# Codeshelf-0005_v01.net
KiCad netlist of a schematic drawn in EAGLE
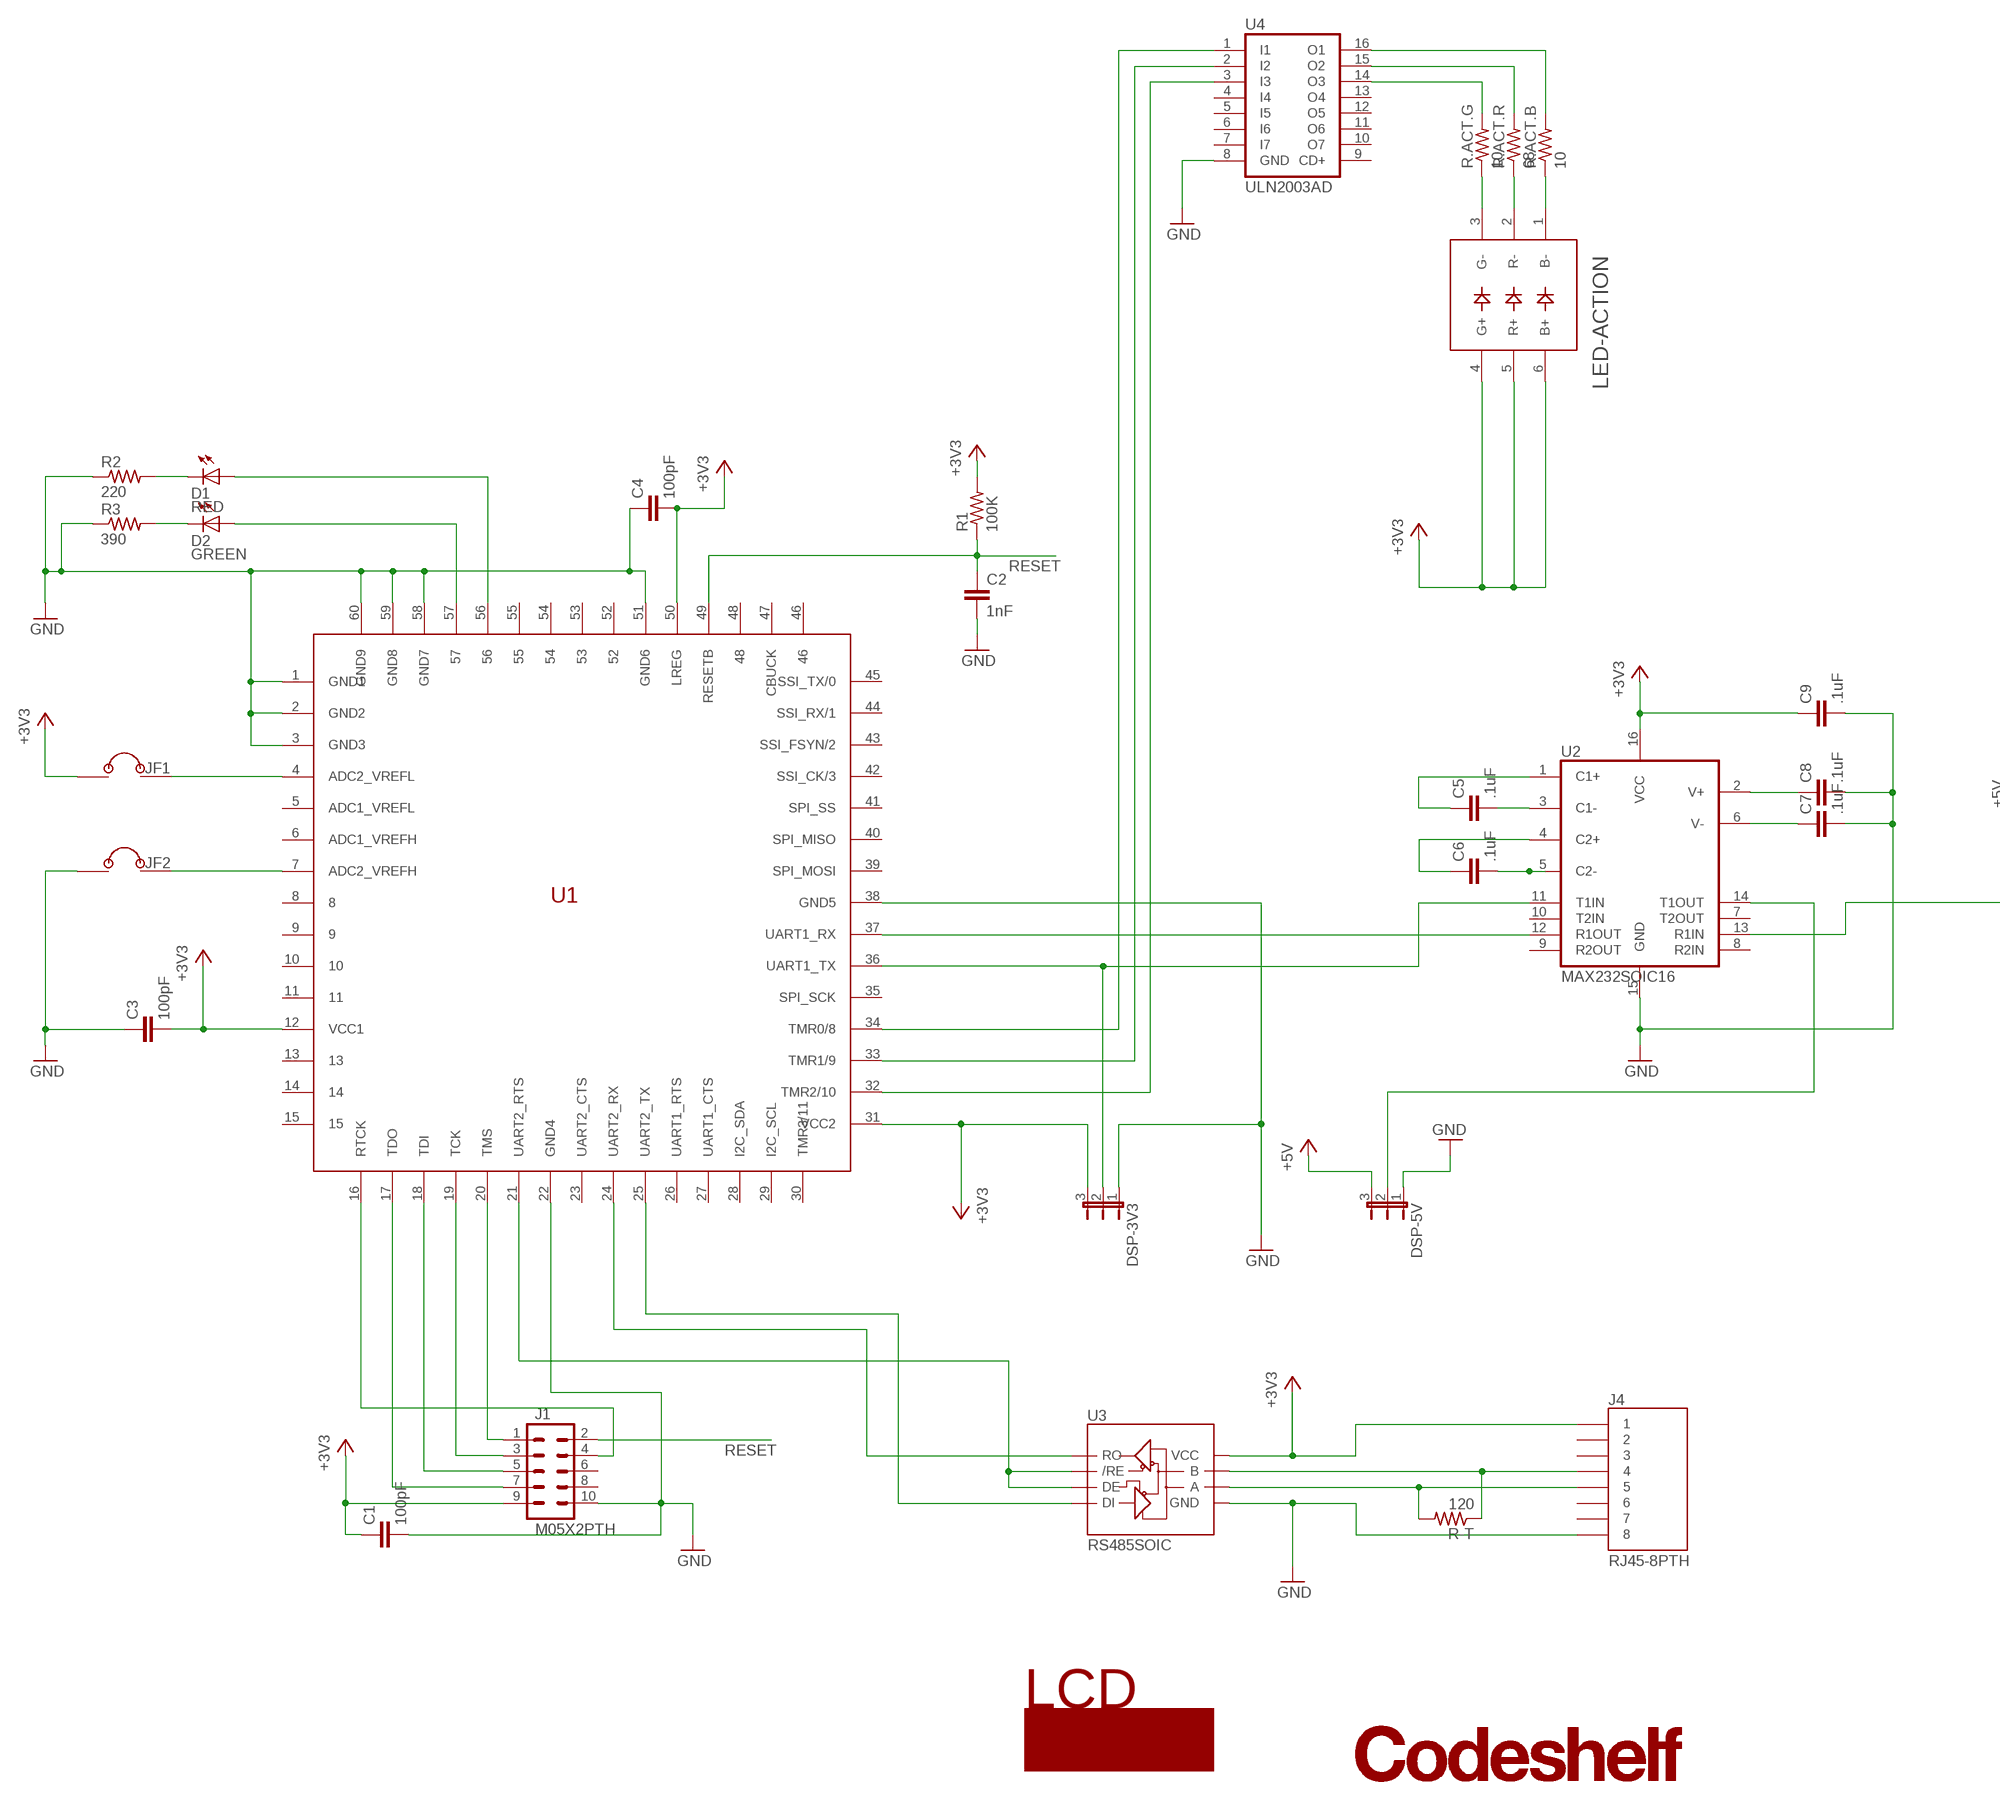
[diagram p0: schematic, sheet 1, part 1 of 2]
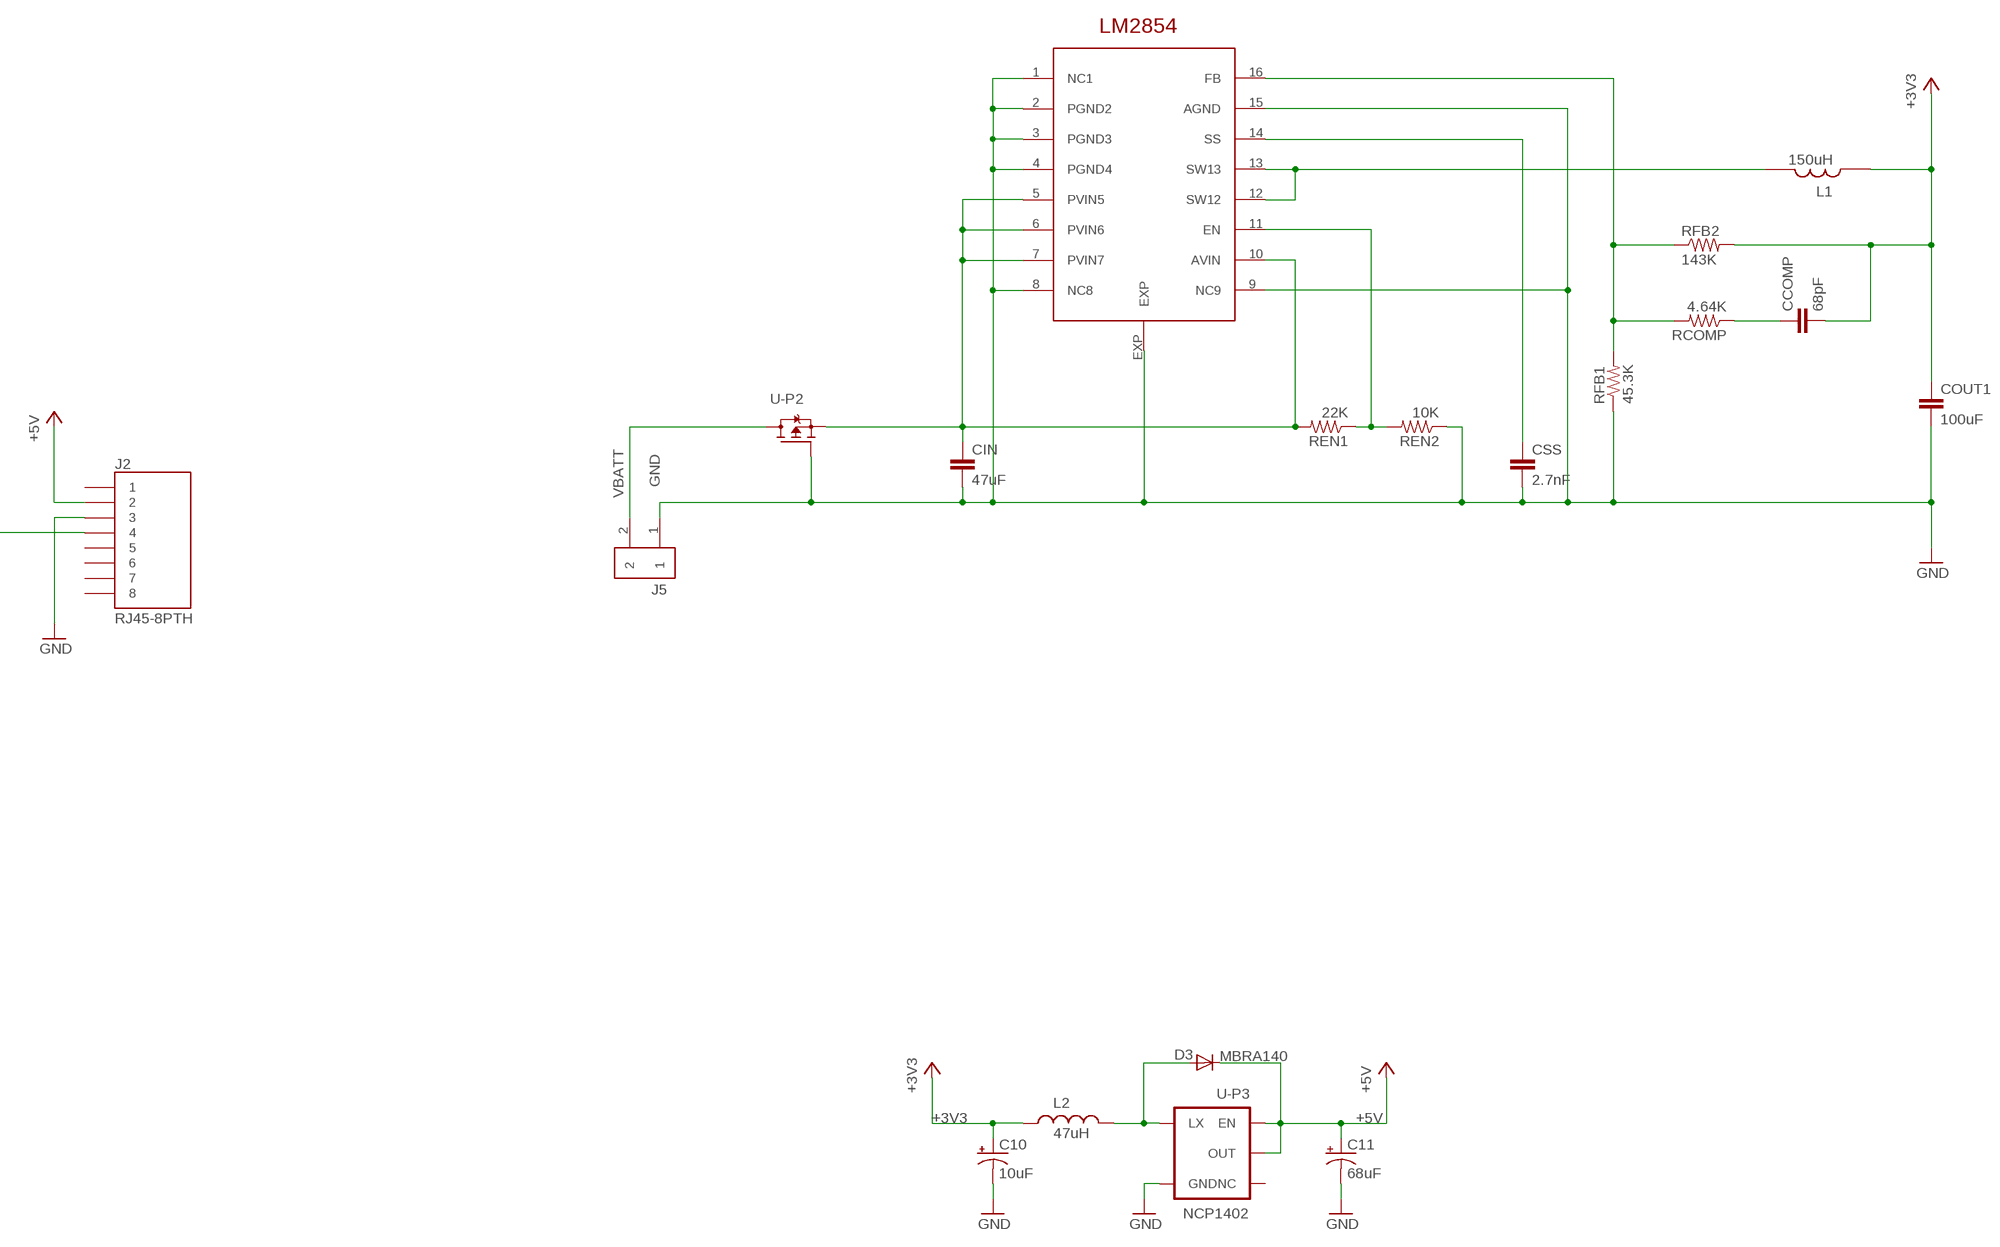
[diagram p1: schematic, sheet 1, part 2 of 2]

(export (version "E")
  (design (tool "Eeschema 10.0.6"))
  (components
    (comp (ref "C1")
      (value "100pF")
      (footprint "eagle-import:C0603")
      (libsource (lib "eagle-import") (part "RF-C0603"))
    )
    (comp (ref "C2")
      (value "1nF")
      (footprint "eagle-import:C0603")
      (libsource (lib "eagle-import") (part "RF-C0603"))
    )
    (comp (ref "C3")
      (value "100pF")
      (footprint "eagle-import:C0603")
      (libsource (lib "eagle-import") (part "RF-C0603"))
    )
    (comp (ref "C4")
      (value "100pF")
      (footprint "eagle-import:C0603")
      (libsource (lib "eagle-import") (part "RF-C0603"))
    )
    (comp (ref "C5")
      (value ".1uF")
      (footprint "eagle-import:C0402")
      (libsource (lib "eagle-import") (part "RF-C0402"))
    )
    (comp (ref "C6")
      (value ".1uF")
      (footprint "eagle-import:C0402")
      (libsource (lib "eagle-import") (part "RF-C0402"))
    )
    (comp (ref "C7")
      (value ".1uF")
      (footprint "eagle-import:C0402")
      (libsource (lib "eagle-import") (part "RF-C0402"))
    )
    (comp (ref "C8")
      (value ".1uF")
      (footprint "eagle-import:C0402")
      (libsource (lib "eagle-import") (part "RF-C0402"))
    )
    (comp (ref "C9")
      (value ".1uF")
      (footprint "eagle-import:C0402")
      (libsource (lib "eagle-import") (part "RF-C0402"))
    )
    (comp (ref "C10")
      (value "10uF")
      (footprint "eagle-import:EIA3216")
      (libsource (lib "eagle-import") (part "CAP_POL1206"))
    )
    (comp (ref "C11")
      (value "68uF")
      (footprint "eagle-import:EIA3528")
      (libsource (lib "eagle-import") (part "CAP_POL3528"))
    )
    (comp (ref "CCOMP")
      (value "68pF")
      (footprint "eagle-import:C0805")
      (libsource (lib "eagle-import") (part "RF-C0805"))
    )
    (comp (ref "CIN")
      (value "47uF")
      (footprint "eagle-import:C1210K")
      (libsource (lib "eagle-import") (part "RF-C1210"))
    )
    (comp (ref "COUT1")
      (value "100uF")
      (footprint "eagle-import:C1210K")
      (libsource (lib "eagle-import") (part "RF-C1210"))
    )
    (comp (ref "CSS")
      (value "2.7nF")
      (footprint "eagle-import:C0805")
      (libsource (lib "eagle-import") (part "RF-C0805"))
    )
    (comp (ref "D1")
      (value "RED")
      (footprint "eagle-import:CHIP-LED0805")
      (libsource (lib "eagle-import") (part "LEDCHIP-LED0805"))
    )
    (comp (ref "D2")
      (value "GREEN")
      (footprint "eagle-import:CHIP-LED0805")
      (libsource (lib "eagle-import") (part "LEDCHIP-LED0805"))
    )
    (comp (ref "D3")
      (value "MBRA140")
      (footprint "eagle-import:SMA-DIODE")
      (libsource (lib "eagle-import") (part "DIODESMA"))
    )
    (comp (ref "DSP-3V3")
      (value "JUMPER-3PTH")
      (footprint "eagle-import:1X03")
      (libsource (lib "eagle-import") (part "JUMPER-3PTH"))
    )
    (comp (ref "DSP-5V")
      (value "JUMPER-3PTH")
      (footprint "eagle-import:1X03")
      (libsource (lib "eagle-import") (part "JUMPER-3PTH"))
    )
    (comp (ref "J1")
      (value "M05X2PTH")
      (footprint "eagle-import:AVR_ICSP")
      (libsource (lib "eagle-import") (part "M05X2PTH"))
    )
    (comp (ref "J2")
      (value "RJ45-8PTH")
      (footprint "eagle-import:RJ45-8")
      (libsource (lib "eagle-import") (part "RJ45-8PTH"))
    )
    (comp (ref "J4")
      (value "RJ45-8PTH")
      (footprint "eagle-import:RJ45-8")
      (libsource (lib "eagle-import") (part "RJ45-8PTH"))
    )
    (comp (ref "J5")
      (value "HEADER-2X-2.54MM")
      (footprint "eagle-import:HEADER-2X-RA-2.54MM")
      (libsource (lib "eagle-import") (part "HEADER-2X-2.54MM"))
    )
    (comp (ref "JF1")
      (value "JUMPER-2X-SMT-VIA")
      (footprint "eagle-import:JUMPER-VIA-2X")
      (libsource (lib "eagle-import") (part "JUMPER-2X-SMT-VIA"))
    )
    (comp (ref "JF2")
      (value "JUMPER-2X-SMT-VIA")
      (footprint "eagle-import:JUMPER-VIA-2X")
      (libsource (lib "eagle-import") (part "JUMPER-2X-SMT-VIA"))
    )
    (comp (ref "L1")
      (value "150uH")
      (footprint "eagle-import:SLF10165")
      (libsource (lib "eagle-import") (part "INDUCTOR-SMD-UNUSUAL-SLF10165"))
    )
    (comp (ref "L2")
      (value "47uH")
      (footprint "eagle-import:CR54")
      (libsource (lib "eagle-import") (part "INDUCTORCR54"))
    )
    (comp (ref "LCD")
      (value "LCD-SPARKFUN")
      (footprint "eagle-import:LCD-20X4-SPARKFUN")
      (libsource (lib "eagle-import") (part "LCD-SPARKFUN20X4"))
    )
    (comp (ref "LED-ACTION")
      (value "LED5060A")
      (footprint "eagle-import:PLCC-6")
      (libsource (lib "eagle-import") (part "LED5060A"))
    )
    (comp (ref "LOGO")
      (value "CODESHELF-LOGO")
      (footprint "eagle-import:CODESHELF-LOGO")
      (libsource (lib "eagle-import") (part "CODESHELF-LOGO"))
    )
    (comp (ref "R-T")
      (value "120")
      (footprint "eagle-import:RF-R0402")
      (libsource (lib "eagle-import") (part "RF-R0402"))
    )
    (comp (ref "R.ACT.B")
      (value "10")
      (footprint "eagle-import:RF-R0402")
      (libsource (lib "eagle-import") (part "RF-R0402"))
    )
    (comp (ref "R.ACT.G")
      (value "10")
      (footprint "eagle-import:RF-R0402")
      (libsource (lib "eagle-import") (part "RF-R0402"))
    )
    (comp (ref "R.ACT.R")
      (value "68")
      (footprint "eagle-import:RF-R0402")
      (libsource (lib "eagle-import") (part "RF-R0402"))
    )
    (comp (ref "R1")
      (value "100K")
      (footprint "eagle-import:RF-R0402")
      (libsource (lib "eagle-import") (part "RF-R0402"))
    )
    (comp (ref "R2")
      (value "220")
      (footprint "eagle-import:RF-R0402")
      (libsource (lib "eagle-import") (part "RF-R0402"))
    )
    (comp (ref "R3")
      (value "390")
      (footprint "eagle-import:RF-R0402")
      (libsource (lib "eagle-import") (part "RF-R0402"))
    )
    (comp (ref "RCOMP")
      (value "4.64K")
      (footprint "eagle-import:RF-R0402")
      (libsource (lib "eagle-import") (part "RF-R0402"))
    )
    (comp (ref "REN1")
      (value "22K")
      (footprint "eagle-import:RF-R0402")
      (libsource (lib "eagle-import") (part "RF-R0402"))
    )
    (comp (ref "REN2")
      (value "10K")
      (footprint "eagle-import:RF-R0402")
      (libsource (lib "eagle-import") (part "RF-R0402"))
    )
    (comp (ref "RFB1")
      (value "45.3K")
      (footprint "eagle-import:RF-R0402")
      (libsource (lib "eagle-import") (part "RF-R0402"))
    )
    (comp (ref "RFB2")
      (value "143K")
      (footprint "eagle-import:RF-R0402")
      (libsource (lib "eagle-import") (part "RF-R0402"))
    )
    (comp (ref "U-P1")
      (value "LM2854MH")
      (footprint "eagle-import:HTSSOP16PWP")
      (libsource (lib "eagle-import") (part "LM2854MH"))
    )
    (comp (ref "U-P2")
      (value "PCHANNEL-MOSFET-DPAK")
      (footprint "eagle-import:DPAK")
      (libsource (lib "eagle-import") (part "PCHANNEL-MOSFET-DPAK"))
    )
    (comp (ref "U-P3")
      (value "NCP1402")
      (footprint "eagle-import:SOT23-5")
      (libsource (lib "eagle-import") (part "V_REG_NCP1400SOT23-5"))
    )
    (comp (ref "U1")
      (value "ZSFM201-1A")
      (footprint "eagle-import:ZSFM201-1")
      (libsource (lib "eagle-import") (part "ZSFM201-1A"))
    )
    (comp (ref "U2")
      (value "MAX232SOIC16")
      (footprint "eagle-import:SO016")
      (libsource (lib "eagle-import") (part "MAX232SOIC16"))
    )
    (comp (ref "U3")
      (value "RS485SOIC")
      (footprint "eagle-import:SO08")
      (libsource (lib "eagle-import") (part "RS485SOIC"))
    )
    (comp (ref "U4")
      (value "ULN2003AD")
      (footprint "eagle-import:SO16")
      (libsource (lib "eagle-import") (part "ULN2003AD"))
    )
  )
  (nets
    (net (code "1") (name "+3V3") (class "Default")
      (node (ref "C1") (pin "1") (pinfunction "1_1") (pintype "passive"))
      (node (ref "C10") (pin "A") (pinfunction "+_A") (pintype "passive"))
      (node (ref "C3") (pin "2") (pinfunction "2_2") (pintype "passive"))
      (node (ref "C4") (pin "2") (pinfunction "2_2") (pintype "passive"))
      (node (ref "C9") (pin "1") (pinfunction "1_1") (pintype "passive"))
      (node (ref "CCOMP") (pin "2") (pinfunction "2_2") (pintype "passive"))
      (node (ref "COUT1") (pin "1") (pinfunction "1_1") (pintype "passive"))
      (node (ref "DSP-3V3") (pin "3") (pinfunction "3_3") (pintype "passive"))
      (node (ref "J1") (pin "9") (pinfunction "9_9") (pintype "passive"))
      (node (ref "J4") (pin "1") (pinfunction "1_1") (pintype "bidirectional"))
      (node (ref "JF1") (pin "1") (pinfunction "1_1") (pintype "bidirectional"))
      (node (ref "L1") (pin "2") (pinfunction "2_2") (pintype "bidirectional"))
      (node (ref "L2") (pin "P$1") (pinfunction "1_P$1") (pintype "passive"))
      (node (ref "LED-ACTION") (pin "4") (pinfunction "G+_4") (pintype "bidirectional"))
      (node (ref "LED-ACTION") (pin "5") (pinfunction "R+_5") (pintype "bidirectional"))
      (node (ref "LED-ACTION") (pin "6") (pinfunction "B+_6") (pintype "bidirectional"))
      (node (ref "R1") (pin "2") (pinfunction "2_2") (pintype "passive"))
      (node (ref "RFB2") (pin "2") (pinfunction "2_2") (pintype "passive"))
      (node (ref "U1") (pin "12") (pinfunction "VCC1_12") (pintype "power_in"))
      (node (ref "U1") (pin "31") (pinfunction "VCC2_31") (pintype "power_in"))
      (node (ref "U1") (pin "50") (pinfunction "LREG_50") (pintype "bidirectional"))
      (node (ref "U2") (pin "16") (pinfunction "VCC_16") (pintype "bidirectional"))
      (node (ref "U3") (pin "8") (pinfunction "VCC_8") (pintype "bidirectional"))
    )
    (net (code "2") (name "+5V") (class "Default")
      (node (ref "C11") (pin "A") (pinfunction "+_A") (pintype "passive"))
      (node (ref "D3") (pin "C") (pinfunction "C_C") (pintype "passive"))
      (node (ref "DSP-5V") (pin "3") (pinfunction "3_3") (pintype "passive"))
      (node (ref "J2") (pin "2") (pinfunction "2_2") (pintype "bidirectional"))
      (node (ref "U-P3") (pin "1") (pinfunction "EN_1") (pintype "input"))
      (node (ref "U-P3") (pin "2") (pinfunction "OUT_2") (pintype "passive"))
    )
    (net (code "3") (name "/RESET") (class "Default")
      (node (ref "C2") (pin "1") (pinfunction "1_1") (pintype "passive"))
      (node (ref "J1") (pin "2") (pinfunction "2_2") (pintype "passive"))
      (node (ref "R1") (pin "1") (pinfunction "1_1") (pintype "passive"))
      (node (ref "U1") (pin "49") (pinfunction "RESETB_49") (pintype "bidirectional"))
    )
    (net (code "4") (name "/VBATT") (class "Default")
      (node (ref "J5") (pin "2") (pinfunction "2_2") (pintype "bidirectional"))
      (node (ref "U-P2") (pin "4") (pinfunction "D_4") (pintype "passive"))
    )
    (net (code "5") (name "GND") (class "Default")
      (node (ref "C1") (pin "2") (pinfunction "2_2") (pintype "passive"))
      (node (ref "C10") (pin "C") (pinfunction "-_C") (pintype "passive"))
      (node (ref "C11") (pin "C") (pinfunction "-_C") (pintype "passive"))
      (node (ref "C2") (pin "2") (pinfunction "2_2") (pintype "passive"))
      (node (ref "C3") (pin "1") (pinfunction "1_1") (pintype "passive"))
      (node (ref "C4") (pin "1") (pinfunction "1_1") (pintype "passive"))
      (node (ref "C7") (pin "2") (pinfunction "2_2") (pintype "passive"))
      (node (ref "C8") (pin "2") (pinfunction "2_2") (pintype "passive"))
      (node (ref "C9") (pin "2") (pinfunction "2_2") (pintype "passive"))
      (node (ref "CIN") (pin "2") (pinfunction "2_2") (pintype "passive"))
      (node (ref "COUT1") (pin "2") (pinfunction "2_2") (pintype "passive"))
      (node (ref "CSS") (pin "2") (pinfunction "2_2") (pintype "passive"))
      (node (ref "DSP-3V3") (pin "1") (pinfunction "1_1") (pintype "passive"))
      (node (ref "DSP-5V") (pin "1") (pinfunction "1_1") (pintype "passive"))
      (node (ref "J1") (pin "10") (pinfunction "10_10") (pintype "passive"))
      (node (ref "J2") (pin "3") (pinfunction "3_3") (pintype "bidirectional"))
      (node (ref "J4") (pin "8") (pinfunction "8_8") (pintype "bidirectional"))
      (node (ref "J5") (pin "1") (pinfunction "1_1") (pintype "bidirectional"))
      (node (ref "JF2") (pin "1") (pinfunction "1_1") (pintype "bidirectional"))
      (node (ref "R2") (pin "1") (pinfunction "1_1") (pintype "passive"))
      (node (ref "R3") (pin "1") (pinfunction "1_1") (pintype "passive"))
      (node (ref "REN2") (pin "1") (pinfunction "1_1") (pintype "passive"))
      (node (ref "RFB1") (pin "1") (pinfunction "1_1") (pintype "passive"))
      (node (ref "U-P1") (pin "1") (pinfunction "NC1_1") (pintype "bidirectional"))
      (node (ref "U-P1") (pin "15") (pinfunction "AGND_15") (pintype "bidirectional"))
      (node (ref "U-P1") (pin "2") (pinfunction "PGND2_2") (pintype "bidirectional"))
      (node (ref "U-P1") (pin "3") (pinfunction "PGND3_3") (pintype "bidirectional"))
      (node (ref "U-P1") (pin "4") (pinfunction "PGND4_4") (pintype "bidirectional"))
      (node (ref "U-P1") (pin "8") (pinfunction "NC8_8") (pintype "bidirectional"))
      (node (ref "U-P1") (pin "9") (pinfunction "NC9_9") (pintype "bidirectional"))
      (node (ref "U-P1") (pin "EXP") (pinfunction "EXP_EXP") (pintype "bidirectional"))
      (node (ref "U-P2") (pin "1") (pinfunction "G_1") (pintype "passive"))
      (node (ref "U-P3") (pin "4") (pinfunction "GND_4") (pintype "input"))
      (node (ref "U1") (pin "1") (pinfunction "GND1_1") (pintype "power_in"))
      (node (ref "U1") (pin "2") (pinfunction "GND2_2") (pintype "power_in"))
      (node (ref "U1") (pin "22") (pinfunction "GND4_22") (pintype "power_in"))
      (node (ref "U1") (pin "3") (pinfunction "GND3_3") (pintype "power_in"))
      (node (ref "U1") (pin "38") (pinfunction "GND5_38") (pintype "power_in"))
      (node (ref "U1") (pin "51") (pinfunction "GND6_51") (pintype "power_in"))
      (node (ref "U1") (pin "58") (pinfunction "GND7_58") (pintype "power_in"))
      (node (ref "U1") (pin "59") (pinfunction "GND8_59") (pintype "power_in"))
      (node (ref "U1") (pin "60") (pinfunction "GND9_60") (pintype "power_in"))
      (node (ref "U2") (pin "15") (pinfunction "GND_15") (pintype "bidirectional"))
      (node (ref "U3") (pin "5") (pinfunction "GND_5") (pintype "bidirectional"))
      (node (ref "U4") (pin "8") (pinfunction "GND_8") (pintype "power_in"))
    )
    (net (code "6") (name "Net-(CCOMP-Pad1)") (class "Default")
      (node (ref "CCOMP") (pin "1") (pinfunction "1_1") (pintype "passive"))
      (node (ref "RCOMP") (pin "1") (pinfunction "1_1") (pintype "passive"))
    )
    (net (code "7") (name "Net-(D1-PadA)") (class "Default")
      (node (ref "D1") (pin "A") (pinfunction "A_A") (pintype "passive"))
      (node (ref "U1") (pin "56") (pinfunction "56_56") (pintype "bidirectional"))
    )
    (net (code "8") (name "Net-(D1-PadC)") (class "Default")
      (node (ref "D1") (pin "C") (pinfunction "C_C") (pintype "passive"))
      (node (ref "R2") (pin "2") (pinfunction "2_2") (pintype "passive"))
    )
    (net (code "9") (name "Net-(D2-PadA)") (class "Default")
      (node (ref "D2") (pin "A") (pinfunction "A_A") (pintype "passive"))
      (node (ref "U1") (pin "57") (pinfunction "57_57") (pintype "bidirectional"))
    )
    (net (code "10") (name "Net-(D2-PadC)") (class "Default")
      (node (ref "D2") (pin "C") (pinfunction "C_C") (pintype "passive"))
      (node (ref "R3") (pin "2") (pinfunction "2_2") (pintype "passive"))
    )
    (net (code "11") (name "Net-(L2-2)") (class "Default")
      (node (ref "D3") (pin "A") (pinfunction "A_A") (pintype "passive"))
      (node (ref "L2") (pin "P$2") (pinfunction "2_P$2") (pintype "passive"))
      (node (ref "U-P3") (pin "5") (pinfunction "LX_5") (pintype "input"))
    )
    (net (code "12") (name "Net-(LED-ACTION-B-)") (class "Default")
      (node (ref "LED-ACTION") (pin "1") (pinfunction "B-_1") (pintype "bidirectional"))
      (node (ref "R.ACT.B") (pin "1") (pinfunction "1_1") (pintype "passive"))
    )
    (net (code "13") (name "Net-(LED-ACTION-G-)") (class "Default")
      (node (ref "LED-ACTION") (pin "3") (pinfunction "G-_3") (pintype "bidirectional"))
      (node (ref "R.ACT.G") (pin "1") (pinfunction "1_1") (pintype "passive"))
    )
    (net (code "14") (name "Net-(LED-ACTION-R-)") (class "Default")
      (node (ref "LED-ACTION") (pin "2") (pinfunction "R-_2") (pintype "bidirectional"))
      (node (ref "R.ACT.R") (pin "1") (pinfunction "1_1") (pintype "passive"))
    )
    (net (code "15") (name "Net-(U-P1-AVIN)") (class "Default")
      (node (ref "CIN") (pin "1") (pinfunction "1_1") (pintype "passive"))
      (node (ref "REN1") (pin "2") (pinfunction "2_2") (pintype "passive"))
      (node (ref "U-P1") (pin "10") (pinfunction "AVIN_10") (pintype "bidirectional"))
      (node (ref "U-P1") (pin "5") (pinfunction "PVIN5_5") (pintype "bidirectional"))
      (node (ref "U-P1") (pin "6") (pinfunction "PVIN6_6") (pintype "bidirectional"))
      (node (ref "U-P1") (pin "7") (pinfunction "PVIN7_7") (pintype "bidirectional"))
      (node (ref "U-P2") (pin "3") (pinfunction "S_3") (pintype "passive"))
    )
    (net (code "16") (name "Net-(U-P1-EN)") (class "Default")
      (node (ref "REN1") (pin "1") (pinfunction "1_1") (pintype "passive"))
      (node (ref "REN2") (pin "2") (pinfunction "2_2") (pintype "passive"))
      (node (ref "U-P1") (pin "11") (pinfunction "EN_11") (pintype "bidirectional"))
    )
    (net (code "17") (name "Net-(U-P1-FB)") (class "Default")
      (node (ref "RCOMP") (pin "2") (pinfunction "2_2") (pintype "passive"))
      (node (ref "RFB1") (pin "2") (pinfunction "2_2") (pintype "passive"))
      (node (ref "RFB2") (pin "1") (pinfunction "1_1") (pintype "passive"))
      (node (ref "U-P1") (pin "16") (pinfunction "FB_16") (pintype "bidirectional"))
    )
    (net (code "18") (name "Net-(U-P1-SS)") (class "Default")
      (node (ref "CSS") (pin "1") (pinfunction "1_1") (pintype "passive"))
      (node (ref "U-P1") (pin "14") (pinfunction "SS_14") (pintype "bidirectional"))
    )
    (net (code "19") (name "Net-(U-P1-SW12)") (class "Default")
      (node (ref "L1") (pin "1") (pinfunction "1_1") (pintype "bidirectional"))
      (node (ref "U-P1") (pin "12") (pinfunction "SW12_12") (pintype "bidirectional"))
      (node (ref "U-P1") (pin "13") (pinfunction "SW13_13") (pintype "bidirectional"))
    )
    (net (code "20") (name "Net-(U1-ADC2_VREFH)") (class "Default")
      (node (ref "JF2") (pin "2") (pinfunction "2_2") (pintype "bidirectional"))
      (node (ref "U1") (pin "7") (pinfunction "ADC2_VREFH_7") (pintype "bidirectional"))
    )
    (net (code "21") (name "Net-(U1-ADC2_VREFL)") (class "Default")
      (node (ref "JF1") (pin "2") (pinfunction "2_2") (pintype "bidirectional"))
      (node (ref "U1") (pin "4") (pinfunction "ADC2_VREFL_4") (pintype "bidirectional"))
    )
    (net (code "22") (name "Net-(U1-RTCK)") (class "Default")
      (node (ref "J1") (pin "4") (pinfunction "4_4") (pintype "passive"))
      (node (ref "U1") (pin "16") (pinfunction "RTCK_16") (pintype "bidirectional"))
    )
    (net (code "23") (name "Net-(U1-TCK)") (class "Default")
      (node (ref "J1") (pin "3") (pinfunction "3_3") (pintype "passive"))
      (node (ref "U1") (pin "19") (pinfunction "TCK_19") (pintype "bidirectional"))
    )
    (net (code "24") (name "Net-(U1-TDI)") (class "Default")
      (node (ref "J1") (pin "5") (pinfunction "5_5") (pintype "passive"))
      (node (ref "U1") (pin "18") (pinfunction "TDI_18") (pintype "bidirectional"))
    )
    (net (code "25") (name "Net-(U1-TDO)") (class "Default")
      (node (ref "J1") (pin "7") (pinfunction "7_7") (pintype "passive"))
      (node (ref "U1") (pin "17") (pinfunction "TDO_17") (pintype "bidirectional"))
    )
    (net (code "26") (name "Net-(U1-TMR0{slash}8)") (class "Default")
      (node (ref "U1") (pin "34") (pinfunction "TMR0/8_34") (pintype "bidirectional"))
      (node (ref "U4") (pin "1") (pinfunction "I1_1") (pintype "input"))
    )
    (net (code "27") (name "Net-(U1-TMR1{slash}9)") (class "Default")
      (node (ref "U1") (pin "33") (pinfunction "TMR1/9_33") (pintype "bidirectional"))
      (node (ref "U4") (pin "2") (pinfunction "I2_2") (pintype "input"))
    )
    (net (code "28") (name "Net-(U1-TMR2{slash}10)") (class "Default")
      (node (ref "U1") (pin "32") (pinfunction "TMR2/10_32") (pintype "bidirectional"))
      (node (ref "U4") (pin "3") (pinfunction "I3_3") (pintype "input"))
    )
    (net (code "29") (name "Net-(U1-TMS)") (class "Default")
      (node (ref "J1") (pin "1") (pinfunction "1_1") (pintype "passive"))
      (node (ref "U1") (pin "20") (pinfunction "TMS_20") (pintype "bidirectional"))
    )
    (net (code "30") (name "Net-(U1-UART1_RX)") (class "Default")
      (node (ref "U1") (pin "37") (pinfunction "UART1_RX_37") (pintype "bidirectional"))
      (node (ref "U2") (pin "12") (pinfunction "R1OUT_12") (pintype "output"))
    )
    (net (code "31") (name "Net-(U1-UART1_TX)") (class "Default")
      (node (ref "DSP-3V3") (pin "2") (pinfunction "2_2") (pintype "passive"))
      (node (ref "U1") (pin "36") (pinfunction "UART1_TX_36") (pintype "bidirectional"))
      (node (ref "U2") (pin "11") (pinfunction "T1IN_11") (pintype "input"))
    )
    (net (code "32") (name "Net-(U1-UART2_RTS)") (class "Default")
      (node (ref "U1") (pin "21") (pinfunction "UART2_RTS_21") (pintype "bidirectional"))
      (node (ref "U3") (pin "2") (pinfunction "/RE_2") (pintype "bidirectional"))
      (node (ref "U3") (pin "3") (pinfunction "DE_3") (pintype "bidirectional"))
    )
    (net (code "33") (name "Net-(U1-UART2_RX)") (class "Default")
      (node (ref "U1") (pin "24") (pinfunction "UART2_RX_24") (pintype "bidirectional"))
      (node (ref "U3") (pin "1") (pinfunction "RO_1") (pintype "bidirectional"))
    )
    (net (code "34") (name "Net-(U1-UART2_TX)") (class "Default")
      (node (ref "U1") (pin "25") (pinfunction "UART2_TX_25") (pintype "bidirectional"))
      (node (ref "U3") (pin "4") (pinfunction "DI_4") (pintype "bidirectional"))
    )
    (net (code "35") (name "Net-(U2-C1+)") (class "Default")
      (node (ref "C5") (pin "1") (pinfunction "1_1") (pintype "passive"))
      (node (ref "U2") (pin "1") (pinfunction "C1+_1") (pintype "bidirectional"))
    )
    (net (code "36") (name "Net-(U2-C1-)") (class "Default")
      (node (ref "C5") (pin "2") (pinfunction "2_2") (pintype "passive"))
      (node (ref "U2") (pin "3") (pinfunction "C1-_3") (pintype "bidirectional"))
    )
    (net (code "37") (name "Net-(U2-C2+)") (class "Default")
      (node (ref "C6") (pin "1") (pinfunction "1_1") (pintype "passive"))
      (node (ref "U2") (pin "4") (pinfunction "C2+_4") (pintype "bidirectional"))
    )
    (net (code "38") (name "Net-(U2-C2-)") (class "Default")
      (node (ref "C6") (pin "2") (pinfunction "2_2") (pintype "passive"))
      (node (ref "U2") (pin "5") (pinfunction "C2-_5") (pintype "bidirectional"))
    )
    (net (code "39") (name "Net-(U2-R1IN)") (class "Default")
      (node (ref "J2") (pin "4") (pinfunction "4_4") (pintype "bidirectional"))
      (node (ref "U2") (pin "13") (pinfunction "R1IN_13") (pintype "input"))
    )
    (net (code "40") (name "Net-(U2-T1OUT)") (class "Default")
      (node (ref "DSP-5V") (pin "2") (pinfunction "2_2") (pintype "passive"))
      (node (ref "U2") (pin "14") (pinfunction "T1OUT_14") (pintype "output"))
    )
    (net (code "41") (name "Net-(U2-V+)") (class "Default")
      (node (ref "C8") (pin "1") (pinfunction "1_1") (pintype "passive"))
      (node (ref "U2") (pin "2") (pinfunction "V+_2") (pintype "bidirectional"))
    )
    (net (code "42") (name "Net-(U2-V-)") (class "Default")
      (node (ref "C7") (pin "1") (pinfunction "1_1") (pintype "passive"))
      (node (ref "U2") (pin "6") (pinfunction "V-_6") (pintype "bidirectional"))
    )
    (net (code "43") (name "Net-(U3-A)") (class "Default")
      (node (ref "J4") (pin "5") (pinfunction "5_5") (pintype "bidirectional"))
      (node (ref "R-T") (pin "2") (pinfunction "2_2") (pintype "passive"))
      (node (ref "U3") (pin "6") (pinfunction "A_6") (pintype "bidirectional"))
    )
    (net (code "44") (name "Net-(U3-B)") (class "Default")
      (node (ref "J4") (pin "4") (pinfunction "4_4") (pintype "bidirectional"))
      (node (ref "R-T") (pin "1") (pinfunction "1_1") (pintype "passive"))
      (node (ref "U3") (pin "7") (pinfunction "B_7") (pintype "bidirectional"))
    )
    (net (code "45") (name "Net-(U4-O1)") (class "Default")
      (node (ref "R.ACT.B") (pin "2") (pinfunction "2_2") (pintype "passive"))
      (node (ref "U4") (pin "16") (pinfunction "O1_16") (pintype "open_collector"))
    )
    (net (code "46") (name "Net-(U4-O2)") (class "Default")
      (node (ref "R.ACT.R") (pin "2") (pinfunction "2_2") (pintype "passive"))
      (node (ref "U4") (pin "15") (pinfunction "O2_15") (pintype "open_collector"))
    )
    (net (code "47") (name "Net-(U4-O3)") (class "Default")
      (node (ref "R.ACT.G") (pin "2") (pinfunction "2_2") (pintype "passive"))
      (node (ref "U4") (pin "14") (pinfunction "O3_14") (pintype "open_collector"))
    )
    (net (code "48") (name "unconnected-(J1-Pad6)") (class "Default")
      (node (ref "J1") (pin "6") (pinfunction "6_6") (pintype "passive"))
    )
    (net (code "49") (name "unconnected-(J1-Pad8)") (class "Default")
      (node (ref "J1") (pin "8") (pinfunction "8_8") (pintype "passive"))
    )
    (net (code "50") (name "unconnected-(J2-Pad1)") (class "Default")
      (node (ref "J2") (pin "1") (pinfunction "1_1") (pintype "bidirectional"))
    )
    (net (code "51") (name "unconnected-(J2-Pad5)") (class "Default")
      (node (ref "J2") (pin "5") (pinfunction "5_5") (pintype "bidirectional"))
    )
    (net (code "52") (name "unconnected-(J2-Pad6)") (class "Default")
      (node (ref "J2") (pin "6") (pinfunction "6_6") (pintype "bidirectional"))
    )
    (net (code "53") (name "unconnected-(J2-Pad7)") (class "Default")
      (node (ref "J2") (pin "7") (pinfunction "7_7") (pintype "bidirectional"))
    )
    (net (code "54") (name "unconnected-(J2-Pad8)") (class "Default")
      (node (ref "J2") (pin "8") (pinfunction "8_8") (pintype "bidirectional"))
    )
    (net (code "55") (name "unconnected-(J4-Pad2)") (class "Default")
      (node (ref "J4") (pin "2") (pinfunction "2_2") (pintype "bidirectional"))
    )
    (net (code "56") (name "unconnected-(J4-Pad3)") (class "Default")
      (node (ref "J4") (pin "3") (pinfunction "3_3") (pintype "bidirectional"))
    )
    (net (code "57") (name "unconnected-(J4-Pad6)") (class "Default")
      (node (ref "J4") (pin "6") (pinfunction "6_6") (pintype "bidirectional"))
    )
    (net (code "58") (name "unconnected-(J4-Pad7)") (class "Default")
      (node (ref "J4") (pin "7") (pinfunction "7_7") (pintype "bidirectional"))
    )
    (net (code "59") (name "unconnected-(U-P3-NC-Pad3)") (class "Default")
      (node (ref "U-P3") (pin "3") (pinfunction "NC_3") (pintype "input"))
    )
    (net (code "60") (name "unconnected-(U1-ADC1_VREFH-Pad6)") (class "Default")
      (node (ref "U1") (pin "6") (pinfunction "ADC1_VREFH_6") (pintype "bidirectional"))
    )
    (net (code "61") (name "unconnected-(U1-ADC1_VREFL-Pad5)") (class "Default")
      (node (ref "U1") (pin "5") (pinfunction "ADC1_VREFL_5") (pintype "bidirectional"))
    )
    (net (code "62") (name "unconnected-(U1-CBUCK-Pad47)") (class "Default")
      (node (ref "U1") (pin "47") (pinfunction "CBUCK_47") (pintype "bidirectional"))
    )
    (net (code "63") (name "unconnected-(U1-I2C_SCL-Pad29)") (class "Default")
      (node (ref "U1") (pin "29") (pinfunction "I2C_SCL_29") (pintype "bidirectional"))
    )
    (net (code "64") (name "unconnected-(U1-I2C_SDA-Pad28)") (class "Default")
      (node (ref "U1") (pin "28") (pinfunction "I2C_SDA_28") (pintype "bidirectional"))
    )
    (net (code "65") (name "unconnected-(U1-Pad8)") (class "Default")
      (node (ref "U1") (pin "8") (pinfunction "8_8") (pintype "bidirectional"))
    )
    (net (code "66") (name "unconnected-(U1-Pad9)") (class "Default")
      (node (ref "U1") (pin "9") (pinfunction "9_9") (pintype "bidirectional"))
    )
    (net (code "67") (name "unconnected-(U1-Pad10)") (class "Default")
      (node (ref "U1") (pin "10") (pinfunction "10_10") (pintype "bidirectional"))
    )
    (net (code "68") (name "unconnected-(U1-Pad11)") (class "Default")
      (node (ref "U1") (pin "11") (pinfunction "11_11") (pintype "bidirectional"))
    )
    (net (code "69") (name "unconnected-(U1-Pad13)") (class "Default")
      (node (ref "U1") (pin "13") (pinfunction "13_13") (pintype "bidirectional"))
    )
    (net (code "70") (name "unconnected-(U1-Pad14)") (class "Default")
      (node (ref "U1") (pin "14") (pinfunction "14_14") (pintype "bidirectional"))
    )
    (net (code "71") (name "unconnected-(U1-Pad15)") (class "Default")
      (node (ref "U1") (pin "15") (pinfunction "15_15") (pintype "bidirectional"))
    )
    (net (code "72") (name "unconnected-(U1-Pad46)") (class "Default")
      (node (ref "U1") (pin "46") (pinfunction "46_46") (pintype "bidirectional"))
    )
    (net (code "73") (name "unconnected-(U1-Pad48)") (class "Default")
      (node (ref "U1") (pin "48") (pinfunction "48_48") (pintype "bidirectional"))
    )
    (net (code "74") (name "unconnected-(U1-Pad52)") (class "Default")
      (node (ref "U1") (pin "52") (pinfunction "52_52") (pintype "bidirectional"))
    )
    (net (code "75") (name "unconnected-(U1-Pad53)") (class "Default")
      (node (ref "U1") (pin "53") (pinfunction "53_53") (pintype "bidirectional"))
    )
    (net (code "76") (name "unconnected-(U1-Pad54)") (class "Default")
      (node (ref "U1") (pin "54") (pinfunction "54_54") (pintype "bidirectional"))
    )
    (net (code "77") (name "unconnected-(U1-Pad55)") (class "Default")
      (node (ref "U1") (pin "55") (pinfunction "55_55") (pintype "bidirectional"))
    )
    (net (code "78") (name "unconnected-(U1-SPI_MISO-Pad40)") (class "Default")
      (node (ref "U1") (pin "40") (pinfunction "SPI_MISO_40") (pintype "bidirectional"))
    )
    (net (code "79") (name "unconnected-(U1-SPI_MOSI-Pad39)") (class "Default")
      (node (ref "U1") (pin "39") (pinfunction "SPI_MOSI_39") (pintype "bidirectional"))
    )
    (net (code "80") (name "unconnected-(U1-SPI_SCK-Pad35)") (class "Default")
      (node (ref "U1") (pin "35") (pinfunction "SPI_SCK_35") (pintype "bidirectional"))
    )
    (net (code "81") (name "unconnected-(U1-SPI_SS-Pad41)") (class "Default")
      (node (ref "U1") (pin "41") (pinfunction "SPI_SS_41") (pintype "bidirectional"))
    )
    (net (code "82") (name "unconnected-(U1-SSI_CK{slash}3-Pad42)") (class "Default")
      (node (ref "U1") (pin "42") (pinfunction "SSI_CK/3_42") (pintype "bidirectional"))
    )
    (net (code "83") (name "unconnected-(U1-SSI_FSYN{slash}2-Pad43)") (class "Default")
      (node (ref "U1") (pin "43") (pinfunction "SSI_FSYN/2_43") (pintype "bidirectional"))
    )
    (net (code "84") (name "unconnected-(U1-SSI_RX{slash}1-Pad44)") (class "Default")
      (node (ref "U1") (pin "44") (pinfunction "SSI_RX/1_44") (pintype "bidirectional"))
    )
    (net (code "85") (name "unconnected-(U1-SSI_TX{slash}0-Pad45)") (class "Default")
      (node (ref "U1") (pin "45") (pinfunction "SSI_TX/0_45") (pintype "bidirectional"))
    )
    (net (code "86") (name "unconnected-(U1-TMR3{slash}11-Pad30)") (class "Default")
      (node (ref "U1") (pin "30") (pinfunction "TMR3/11_30") (pintype "bidirectional"))
    )
    (net (code "87") (name "unconnected-(U1-UART1_CTS-Pad27)") (class "Default")
      (node (ref "U1") (pin "27") (pinfunction "UART1_CTS_27") (pintype "bidirectional"))
    )
    (net (code "88") (name "unconnected-(U1-UART1_RTS-Pad26)") (class "Default")
      (node (ref "U1") (pin "26") (pinfunction "UART1_RTS_26") (pintype "bidirectional"))
    )
    (net (code "89") (name "unconnected-(U1-UART2_CTS-Pad23)") (class "Default")
      (node (ref "U1") (pin "23") (pinfunction "UART2_CTS_23") (pintype "bidirectional"))
    )
    (net (code "90") (name "unconnected-(U2-R2IN-Pad8)") (class "Default")
      (node (ref "U2") (pin "8") (pinfunction "R2IN_8") (pintype "input"))
    )
    (net (code "91") (name "unconnected-(U2-R2OUT-Pad9)") (class "Default")
      (node (ref "U2") (pin "9") (pinfunction "R2OUT_9") (pintype "output"))
    )
    (net (code "92") (name "unconnected-(U2-T2IN-Pad10)") (class "Default")
      (node (ref "U2") (pin "10") (pinfunction "T2IN_10") (pintype "input"))
    )
    (net (code "93") (name "unconnected-(U2-T2OUT-Pad7)") (class "Default")
      (node (ref "U2") (pin "7") (pinfunction "T2OUT_7") (pintype "output"))
    )
    (net (code "94") (name "unconnected-(U4-CD+-Pad9)") (class "Default")
      (node (ref "U4") (pin "9") (pinfunction "CD+_9") (pintype "passive"))
    )
    (net (code "95") (name "unconnected-(U4-I4-Pad4)") (class "Default")
      (node (ref "U4") (pin "4") (pinfunction "I4_4") (pintype "input"))
    )
    (net (code "96") (name "unconnected-(U4-I5-Pad5)") (class "Default")
      (node (ref "U4") (pin "5") (pinfunction "I5_5") (pintype "input"))
    )
    (net (code "97") (name "unconnected-(U4-I6-Pad6)") (class "Default")
      (node (ref "U4") (pin "6") (pinfunction "I6_6") (pintype "input"))
    )
    (net (code "98") (name "unconnected-(U4-I7-Pad7)") (class "Default")
      (node (ref "U4") (pin "7") (pinfunction "I7_7") (pintype "input"))
    )
    (net (code "99") (name "unconnected-(U4-O4-Pad13)") (class "Default")
      (node (ref "U4") (pin "13") (pinfunction "O4_13") (pintype "open_collector"))
    )
    (net (code "100") (name "unconnected-(U4-O5-Pad12)") (class "Default")
      (node (ref "U4") (pin "12") (pinfunction "O5_12") (pintype "open_collector"))
    )
    (net (code "101") (name "unconnected-(U4-O6-Pad11)") (class "Default")
      (node (ref "U4") (pin "11") (pinfunction "O6_11") (pintype "open_collector"))
    )
    (net (code "102") (name "unconnected-(U4-O7-Pad10)") (class "Default")
      (node (ref "U4") (pin "10") (pinfunction "O7_10") (pintype "open_collector"))
    )
  )
)
